# MachRada.net
KiCad netlist of a schematic drawn in Altium Designer
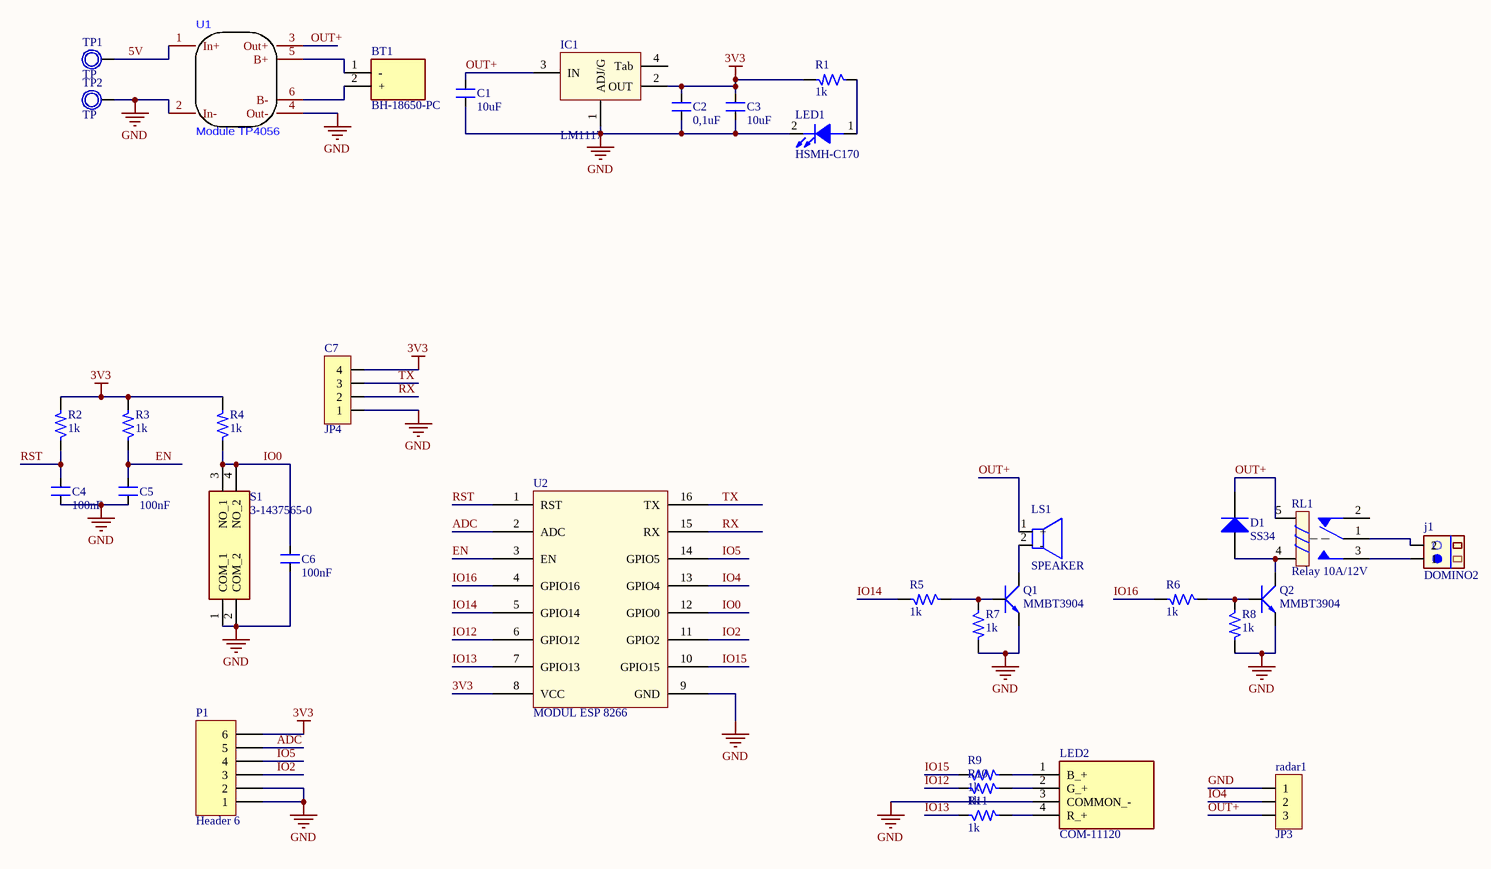
[diagram p0: MachRada.SchDoc]

(export (version "E")
  (design (tool "Eeschema 10.0.6"))
  (components
    (comp (ref "BT1")
      (value "BH-18650-PC")
      (footprint "PIN 18650PC")
      (description "Battery")
      (libsource (lib "thuvienthong") (part "PIN 18650-PC"))
    )
    (comp (ref "C1")
      (value "10uF")
      (footprint "C1206")
      (description "10uF/25V")
      (fields (field (name "DESIGNED BY") "VanDungEvn"))
      (libsource (lib "thuvienthong") (part "CN"))
    )
    (comp (ref "C2")
      (value "0,1uF")
      (footprint "SM-CAP-0805")
      (description "0,1uF/300V")
      (fields (field (name "DESIGNED BY") "VanDungEvn"))
      (libsource (lib "thuvienthong") (part "CN"))
    )
    (comp (ref "C3")
      (value "10uF")
      (footprint "C1206")
      (description "0,1uF/300V")
      (fields (field (name "DESIGNED BY") "VanDungEvn"))
      (libsource (lib "thuvienthong") (part "CN"))
    )
    (comp (ref "C4")
      (value "100nF")
      (footprint "SM-CAP-0805")
      (description "0,1uF/300V")
      (fields (field (name "DESIGNED BY") "VanDungEvn"))
      (libsource (lib "thuvienthong") (part "CN"))
    )
    (comp (ref "C5")
      (value "100nF")
      (footprint "SM-CAP-0805")
      (description "0,1uF/300V")
      (fields (field (name "DESIGNED BY") "VanDungEvn"))
      (libsource (lib "thuvienthong") (part "CN"))
    )
    (comp (ref "C6")
      (value "100nF")
      (footprint "SM-CAP-0805")
      (description "0,1uF/300V")
      (fields (field (name "DESIGNED BY") "VanDungEvn"))
      (libsource (lib "thuvienthong") (part "CN"))
    )
    (comp (ref "C7")
      (value "JP4")
      (footprint "JP4-C1T")
      (description "WR-PHD 2.54 mm Angled Socket Header")
      (fields
        (field (name "MANUFACTURER") "Würth Elektronik eiSos GmbH")
        (field (name "PARTNO") "613004143121")
        (field (name "CREATED BY") "Karrer Zheng")
      )
      (libsource (lib "LIBRARY") (part "JP4"))
    )
    (comp (ref "D1")
      (value "SS34")
      (footprint "DIOT")
      (description "1 Amp General Purpose Rectifier")
      (fields (field (name "PUBLISHER") "Altium Limited"))
      (libsource (lib "thuvienthong") (part "Diode 1N4007"))
    )
    (comp (ref "IC1")
      (value "LM1117")
      (footprint "LM1117-3V3-5V")
      (description "3v3")
      (libsource (lib "thuvienthong") (part "LM1117"))
    )
    (comp (ref "j1")
      (value "DOMINO2")
      (footprint "DOMINO2")
      (libsource (lib "thuvienthong") (part "DOMINO2"))
    )
    (comp (ref "LED1")
      (value "HSMH-C170")
      (footprint "LED")
      (description "Typical GaAs SMD LED")
      (fields (field (name "MANUFACTURER") "Lite-On Inc") (field (name "PUBLISHER") "Hoang Nguyen"))
      (libsource (lib "thuvienthong") (part "LED_1"))
    )
    (comp (ref "LED2")
      (value "COM-11120")
      (footprint "LED RGB 10MM")
      (description "LED")
      (fields (field (name "MOUSER PART NUMBER") "474-COM-11120"))
      (libsource (lib "thuvienthong") (part "LED RGB 10MM"))
    )
    (comp (ref "LS1")
      (value "SPEAKER")
      (footprint "speaker")
      (fields (field (name "PUBLISHER") "Hoang Nguyen"))
      (libsource (lib "hphonglib") (part "SPEAKER"))
    )
    (comp (ref "P1")
      (value "Header 6")
      (footprint "Header 6")
      (description "Header, 6-Pin")
      (fields (field (name "PUBLISHER") "Altium Limited"))
      (libsource (lib "hphonglib") (part "Header 6"))
    )
    (comp (ref "Q1")
      (value "MMBT3904")
      (footprint "MMBT 3904")
      (libsource (lib "thuvienthong") (part "MMBT3904"))
    )
    (comp (ref "Q2")
      (value "MMBT3904")
      (footprint "MMBT 3904")
      (libsource (lib "thuvienthong") (part "MMBT3904"))
    )
    (comp (ref "R1")
      (value "1k")
      (footprint "SM-RES-0805")
      (description "Resistor 1/4W")
      (libsource (lib "thuvienthong") (part "R_1"))
    )
    (comp (ref "R2")
      (value "1k")
      (footprint "SM-RES-0805")
      (description "Resistor 1/4W")
      (libsource (lib "thuvienthong") (part "R_1"))
    )
    (comp (ref "R3")
      (value "1k")
      (footprint "SM-RES-0805")
      (description "Resistor 1/4W")
      (libsource (lib "thuvienthong") (part "R_1"))
    )
    (comp (ref "R4")
      (value "1k")
      (footprint "SM-RES-0805")
      (description "Resistor 1/4W")
      (libsource (lib "thuvienthong") (part "R_1"))
    )
    (comp (ref "R5")
      (value "1k")
      (footprint "SM-RES-0805")
      (description "Resistor 1/4W")
      (libsource (lib "thuvienthong") (part "R_1"))
    )
    (comp (ref "R6")
      (value "1k")
      (footprint "SM-RES-0805")
      (description "Resistor 1/4W")
      (libsource (lib "thuvienthong") (part "R_1"))
    )
    (comp (ref "R7")
      (value "1k")
      (footprint "SM-RES-0805")
      (description "Resistor 1/4W")
      (libsource (lib "thuvienthong") (part "R_1"))
    )
    (comp (ref "R8")
      (value "1k")
      (footprint "SM-RES-0805")
      (description "Resistor 1/4W")
      (libsource (lib "thuvienthong") (part "R_1"))
    )
    (comp (ref "R9")
      (value "1k")
      (footprint "SM-RES-0805")
      (description "Resistor 1/4W")
      (libsource (lib "thuvienthong") (part "R_1"))
    )
    (comp (ref "R10")
      (value "1k")
      (footprint "SM-RES-0805")
      (description "Resistor 1/4W")
      (libsource (lib "thuvienthong") (part "R_1"))
    )
    (comp (ref "R11")
      (value "1k")
      (footprint "SM-RES-0805")
      (description "Resistor 1/4W")
      (libsource (lib "thuvienthong") (part "R_1"))
    )
    (comp (ref "radar1")
      (value "JP3")
      (footprint "JP3-C1T")
      (description "WR-PHD 2.54 mm Angled Socket Header")
      (fields
        (field (name "MANUFACTURER") "Würth Elektronik eiSos GmbH")
        (field (name "PARTNO") "613003143121")
        (field (name "CREATED BY") "Karrer Zheng")
      )
      (libsource (lib "LIBRARY") (part "JP3"))
    )
    (comp (ref "RL1")
      (value "Relay 10A/12V")
      (footprint "RELAY 5")
      (description "Relay SPDT,10A - 5VDC 5 Pin")
      (libsource (lib "LIBRARY") (part "Relay 5"))
    )
    (comp (ref "S1")
      (value "3-1437565-0")
      (footprint "Button SMD")
      (description "Switch")
      (fields (field (name "MOUSER PART NUMBER") "506-3-1437565-0"))
      (libsource (lib "thuvienthong") (part "Button"))
    )
    (comp (ref "TP1")
      (value "TP")
      (footprint "TP1")
      (description "Test Point")
      (libsource (lib "syhaunguyen") (part "TP1"))
    )
    (comp (ref "TP2")
      (value "TP")
      (footprint "TP1")
      (description "Test Point")
      (libsource (lib "syhaunguyen") (part "TP1"))
    )
    (comp (ref "U1")
      (value "Module TP4056")
      (footprint "Module TP4056")
      (libsource (lib "thuvienthong") (part "Module TP4056"))
    )
    (comp (ref "U2")
      (value "MODUL ESP 8266")
      (footprint "esp8622 v7")
      (libsource (lib "thuvienthong") (part "MODUL ESP 8622"))
    )
  )
  (nets
    (net (code "1") (name "/5V") (class "Default")
      (node (ref "TP1") (pin "1") (pinfunction "1_1") (pintype "passive"))
      (node (ref "U1") (pin "1") (pinfunction "In+_1") (pintype "passive"))
    )
    (net (code "2") (name "/ADC") (class "Default")
      (node (ref "P1") (pin "5") (pinfunction "5_5") (pintype "passive"))
      (node (ref "U2") (pin "2") (pinfunction "ADC_2") (pintype "passive"))
    )
    (net (code "3") (name "/EN") (class "Default")
      (node (ref "C5") (pin "1") (pinfunction "1_1") (pintype "passive"))
      (node (ref "R3") (pin "1") (pinfunction "1_1") (pintype "passive"))
      (node (ref "U2") (pin "3") (pinfunction "EN_3") (pintype "passive"))
    )
    (net (code "4") (name "/IO0") (class "Default")
      (node (ref "C6") (pin "1") (pinfunction "1_1") (pintype "passive"))
      (node (ref "R4") (pin "1") (pinfunction "1_1") (pintype "passive"))
      (node (ref "S1") (pin "3") (pinfunction "NO_1_3") (pintype "passive"))
      (node (ref "S1") (pin "4") (pinfunction "NO_2_4") (pintype "passive"))
      (node (ref "U2") (pin "12") (pinfunction "GPIO0_12") (pintype "passive"))
    )
    (net (code "5") (name "/IO2") (class "Default")
      (node (ref "P1") (pin "3") (pinfunction "3_3") (pintype "passive"))
      (node (ref "U2") (pin "11") (pinfunction "GPIO2_11") (pintype "passive"))
    )
    (net (code "6") (name "/IO4") (class "Default")
      (node (ref "U2") (pin "13") (pinfunction "GPIO4_13") (pintype "passive"))
      (node (ref "radar1") (pin "2") (pinfunction "2_2") (pintype "passive"))
    )
    (net (code "7") (name "/IO5") (class "Default")
      (node (ref "P1") (pin "4") (pinfunction "4_4") (pintype "passive"))
      (node (ref "U2") (pin "14") (pinfunction "GPIO5_14") (pintype "passive"))
    )
    (net (code "8") (name "/IO12") (class "Default")
      (node (ref "R10") (pin "1") (pinfunction "1_1") (pintype "passive"))
      (node (ref "U2") (pin "6") (pinfunction "GPIO12_6") (pintype "passive"))
    )
    (net (code "9") (name "/IO13") (class "Default")
      (node (ref "R11") (pin "1") (pinfunction "1_1") (pintype "passive"))
      (node (ref "U2") (pin "7") (pinfunction "GPIO13_7") (pintype "passive"))
    )
    (net (code "10") (name "/IO14") (class "Default")
      (node (ref "R5") (pin "2") (pinfunction "2_2") (pintype "passive"))
      (node (ref "U2") (pin "5") (pinfunction "GPIO14_5") (pintype "passive"))
    )
    (net (code "11") (name "/IO15") (class "Default")
      (node (ref "R9") (pin "1") (pinfunction "1_1") (pintype "passive"))
      (node (ref "U2") (pin "10") (pinfunction "GPIO15_10") (pintype "passive"))
    )
    (net (code "12") (name "/IO16") (class "Default")
      (node (ref "R6") (pin "2") (pinfunction "2_2") (pintype "passive"))
      (node (ref "U2") (pin "4") (pinfunction "GPIO16_4") (pintype "passive"))
    )
    (net (code "13") (name "/OUT+") (class "Default")
      (node (ref "C1") (pin "2") (pinfunction "2_2") (pintype "passive"))
      (node (ref "D1") (pin "2") (pinfunction "K_2") (pintype "passive"))
      (node (ref "IC1") (pin "3") (pinfunction "IN_3") (pintype "passive"))
      (node (ref "LS1") (pin "1") (pinfunction "+_1") (pintype "passive"))
      (node (ref "RL1") (pin "5") (pinfunction "5_5") (pintype "passive"))
      (node (ref "U1") (pin "3") (pinfunction "Out+_3") (pintype "passive"))
      (node (ref "radar1") (pin "3") (pinfunction "3_3") (pintype "passive"))
    )
    (net (code "14") (name "/RST") (class "Default")
      (node (ref "C4") (pin "1") (pinfunction "1_1") (pintype "passive"))
      (node (ref "R2") (pin "1") (pinfunction "1_1") (pintype "passive"))
      (node (ref "U2") (pin "1") (pinfunction "RST_1") (pintype "passive"))
    )
    (net (code "15") (name "/RX") (class "Default")
      (node (ref "C7") (pin "2") (pinfunction "2_2") (pintype "passive"))
      (node (ref "U2") (pin "15") (pinfunction "RX_15") (pintype "passive"))
    )
    (net (code "16") (name "/TX") (class "Default")
      (node (ref "C7") (pin "3") (pinfunction "3_3") (pintype "passive"))
      (node (ref "U2") (pin "16") (pinfunction "TX_16") (pintype "passive"))
    )
    (net (code "17") (name "3V3") (class "Default")
      (node (ref "C2") (pin "2") (pinfunction "2_2") (pintype "passive"))
      (node (ref "C3") (pin "2") (pinfunction "2_2") (pintype "passive"))
      (node (ref "C7") (pin "4") (pinfunction "4_4") (pintype "passive"))
      (node (ref "IC1") (pin "2") (pinfunction "OUT_2") (pintype "passive"))
      (node (ref "P1") (pin "6") (pinfunction "6_6") (pintype "passive"))
      (node (ref "R1") (pin "2") (pinfunction "2_2") (pintype "passive"))
      (node (ref "R2") (pin "2") (pinfunction "2_2") (pintype "passive"))
      (node (ref "R3") (pin "2") (pinfunction "2_2") (pintype "passive"))
      (node (ref "R4") (pin "2") (pinfunction "2_2") (pintype "passive"))
      (node (ref "U2") (pin "8") (pinfunction "VCC_8") (pintype "passive"))
    )
    (net (code "18") (name "GND") (class "Default")
      (node (ref "C1") (pin "1") (pinfunction "1_1") (pintype "passive"))
      (node (ref "C2") (pin "1") (pinfunction "1_1") (pintype "passive"))
      (node (ref "C3") (pin "1") (pinfunction "1_1") (pintype "passive"))
      (node (ref "C4") (pin "2") (pinfunction "2_2") (pintype "passive"))
      (node (ref "C5") (pin "2") (pinfunction "2_2") (pintype "passive"))
      (node (ref "C6") (pin "2") (pinfunction "2_2") (pintype "passive"))
      (node (ref "C7") (pin "1") (pinfunction "1_1") (pintype "passive"))
      (node (ref "IC1") (pin "1") (pinfunction "ADJ/G_1") (pintype "passive"))
      (node (ref "LED1") (pin "2") (pinfunction "K_2") (pintype "passive"))
      (node (ref "LED2") (pin "3") (pinfunction "COMMON_-_3") (pintype "passive"))
      (node (ref "P1") (pin "1") (pinfunction "1_1") (pintype "passive"))
      (node (ref "P1") (pin "2") (pinfunction "2_2") (pintype "passive"))
      (node (ref "Q1") (pin "2") (pinfunction "E_2") (pintype "passive"))
      (node (ref "Q2") (pin "2") (pinfunction "E_2") (pintype "passive"))
      (node (ref "R7") (pin "2") (pinfunction "2_2") (pintype "passive"))
      (node (ref "R8") (pin "2") (pinfunction "2_2") (pintype "passive"))
      (node (ref "S1") (pin "1") (pinfunction "COM_1_1") (pintype "passive"))
      (node (ref "S1") (pin "2") (pinfunction "COM_2_2") (pintype "passive"))
      (node (ref "TP2") (pin "1") (pinfunction "1_1") (pintype "passive"))
      (node (ref "U1") (pin "2") (pinfunction "In-_2") (pintype "passive"))
      (node (ref "U1") (pin "4") (pinfunction "Out-_4") (pintype "passive"))
      (node (ref "U2") (pin "9") (pinfunction "GND_9") (pintype "passive"))
      (node (ref "radar1") (pin "1") (pinfunction "1_1") (pintype "passive"))
    )
    (net (code "19") (name "Net-(BT1-+)") (class "Default")
      (node (ref "BT1") (pin "2") (pinfunction "+_2") (pintype "passive"))
      (node (ref "U1") (pin "6") (pinfunction "B-_6") (pintype "passive"))
    )
    (net (code "20") (name "Net-(BT1--)") (class "Default")
      (node (ref "BT1") (pin "1") (pinfunction "-_1") (pintype "passive"))
      (node (ref "U1") (pin "5") (pinfunction "B+_5") (pintype "passive"))
    )
    (net (code "21") (name "Net-(D1-A)") (class "Default")
      (node (ref "D1") (pin "1") (pinfunction "A_1") (pintype "passive"))
      (node (ref "Q2") (pin "3") (pinfunction "C_3") (pintype "passive"))
      (node (ref "RL1") (pin "4") (pinfunction "4_4") (pintype "passive"))
    )
    (net (code "22") (name "Net-(LED1-A)") (class "Default")
      (node (ref "LED1") (pin "1") (pinfunction "A_1") (pintype "passive"))
      (node (ref "R1") (pin "1") (pinfunction "1_1") (pintype "passive"))
    )
    (net (code "23") (name "Net-(LED2-B_+)") (class "Default")
      (node (ref "LED2") (pin "1") (pinfunction "B_+_1") (pintype "passive"))
      (node (ref "R9") (pin "2") (pinfunction "2_2") (pintype "passive"))
    )
    (net (code "24") (name "Net-(LED2-G_+)") (class "Default")
      (node (ref "LED2") (pin "2") (pinfunction "G_+_2") (pintype "passive"))
      (node (ref "R10") (pin "2") (pinfunction "2_2") (pintype "passive"))
    )
    (net (code "25") (name "Net-(LED2-R_+)") (class "Default")
      (node (ref "LED2") (pin "4") (pinfunction "R_+_4") (pintype "passive"))
      (node (ref "R11") (pin "2") (pinfunction "2_2") (pintype "passive"))
    )
    (net (code "26") (name "Net-(LS1--)") (class "Default")
      (node (ref "LS1") (pin "2") (pinfunction "-_2") (pintype "passive"))
      (node (ref "Q1") (pin "3") (pinfunction "C_3") (pintype "passive"))
    )
    (net (code "27") (name "Net-(Q1-B)") (class "Default")
      (node (ref "Q1") (pin "1") (pinfunction "B_1") (pintype "passive"))
      (node (ref "R5") (pin "1") (pinfunction "1_1") (pintype "passive"))
      (node (ref "R7") (pin "1") (pinfunction "1_1") (pintype "passive"))
    )
    (net (code "28") (name "Net-(Q2-B)") (class "Default")
      (node (ref "Q2") (pin "1") (pinfunction "B_1") (pintype "passive"))
      (node (ref "R6") (pin "1") (pinfunction "1_1") (pintype "passive"))
      (node (ref "R8") (pin "1") (pinfunction "1_1") (pintype "passive"))
    )
    (net (code "29") (name "Net-(RL1-Pad1)") (class "Default")
      (node (ref "RL1") (pin "1") (pinfunction "1_1") (pintype "passive"))
      (node (ref "j1") (pin "2") (pinfunction "2_2") (pintype "passive"))
    )
    (net (code "30") (name "Net-(RL1-Pad3)") (class "Default")
      (node (ref "RL1") (pin "3") (pinfunction "3_3") (pintype "passive"))
      (node (ref "j1") (pin "1") (pinfunction "1_1") (pintype "passive"))
    )
    (net (code "31") (name "unconnected-(IC1-Tab-Pad4)") (class "Default")
      (node (ref "IC1") (pin "4") (pinfunction "Tab_4") (pintype "passive"))
    )
    (net (code "32") (name "unconnected-(RL1-Pad2)") (class "Default")
      (node (ref "RL1") (pin "2") (pinfunction "2_2") (pintype "passive"))
    )
  )
)
